# cerberus.net
KiCad netlist of a schematic drawn in EAGLE
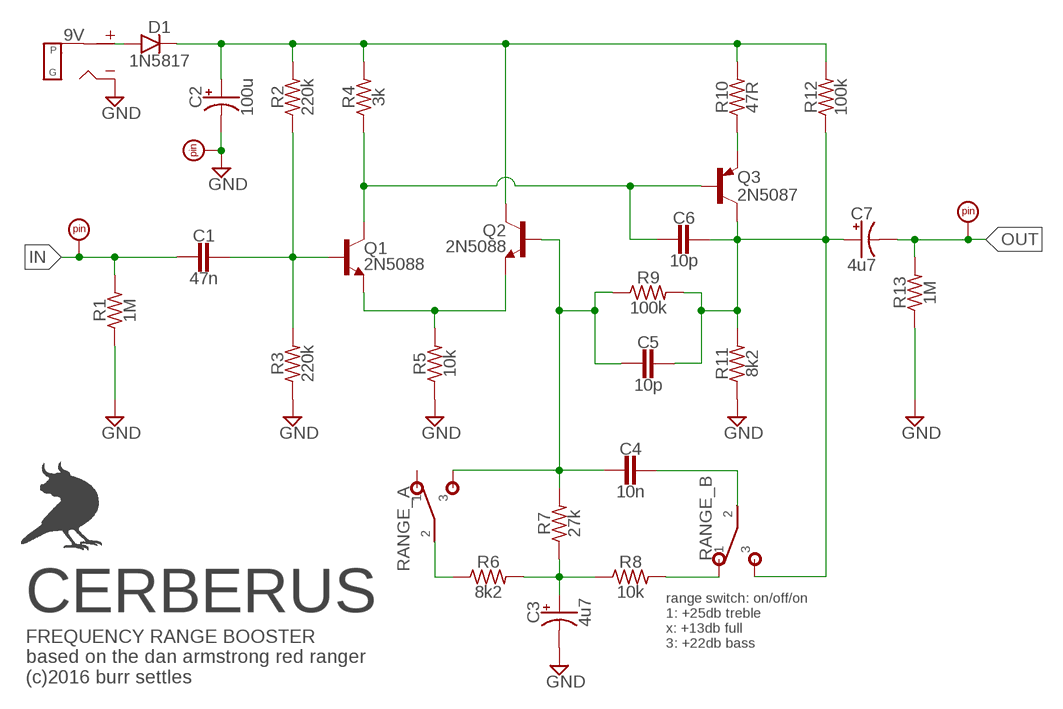
[diagram p0: schematic, sheet 1]

(export (version "E")
  (design (tool "Eeschema 10.0.6"))
  (components
    (comp (ref "9V")
      (value "DC_MONO")
      (footprint "eagle-import:DC")
      (libsource (lib "eagle-import") (part "DC_MONO"))
    )
    (comp (ref "C1")
      (value "47n")
      (footprint "eagle-import:BOX_SMALL")
      (libsource (lib "eagle-import") (part "CER/FILMBOX.1"))
    )
    (comp (ref "C2")
      (value "100u")
      (footprint "eagle-import:050_020_1")
      (libsource (lib "eagle-import") (part "0501"))
    )
    (comp (ref "C3")
      (value "4u7")
      (footprint "eagle-import:050_020_1")
      (libsource (lib "eagle-import") (part "0501"))
    )
    (comp (ref "C4")
      (value "10n")
      (footprint "eagle-import:BOX_SMALL")
      (libsource (lib "eagle-import") (part "CER/FILMBOX.1"))
    )
    (comp (ref "C5")
      (value "10p")
      (footprint "eagle-import:050X030_025_2")
      (libsource (lib "eagle-import") (part "CER/FILM2"))
    )
    (comp (ref "C6")
      (value "10p")
      (footprint "eagle-import:050X030_025_2")
      (libsource (lib "eagle-import") (part "CER/FILM2"))
    )
    (comp (ref "C7")
      (value "4u7")
      (footprint "eagle-import:050_020_1")
      (libsource (lib "eagle-import") (part "0501"))
    )
    (comp (ref "D1")
      (value "1N5817")
      (footprint "eagle-import:DO41-3")
      (libsource (lib "eagle-import") (part "DO41.3"))
    )
    (comp (ref "GND")
      (value "PADRND")
      (footprint "eagle-import:ROUND")
      (libsource (lib "eagle-import") (part "PADRND"))
    )
    (comp (ref "IN")
      (value "PADSQR")
      (footprint "eagle-import:SQUARE")
      (libsource (lib "eagle-import") (part "PADSQR"))
    )
    (comp (ref "OUT")
      (value "PADSQR")
      (footprint "eagle-import:SQUARE")
      (libsource (lib "eagle-import") (part "PADSQR"))
    )
    (comp (ref "Q1")
      (value "2N5088")
      (footprint "eagle-import:TO92-")
      (libsource (lib "eagle-import") (part "2N5088"))
    )
    (comp (ref "Q2")
      (value "2N5088")
      (footprint "eagle-import:TO92-")
      (libsource (lib "eagle-import") (part "2N5088"))
    )
    (comp (ref "Q3")
      (value "2N5087")
      (footprint "eagle-import:TO92-")
      (libsource (lib "eagle-import") (part "2N5087.1"))
    )
    (comp (ref "R1")
      (value "1M")
      (footprint "eagle-import:R0207_3")
      (libsource (lib "eagle-import") (part "R_.3B"))
    )
    (comp (ref "R2")
      (value "220k")
      (footprint "eagle-import:R0207_3")
      (libsource (lib "eagle-import") (part "R_.3B"))
    )
    (comp (ref "R3")
      (value "220k")
      (footprint "eagle-import:R0207_3")
      (libsource (lib "eagle-import") (part "R_.3B"))
    )
    (comp (ref "R4")
      (value "3k")
      (footprint "eagle-import:R0207_3")
      (libsource (lib "eagle-import") (part "R_.3B"))
    )
    (comp (ref "R5")
      (value "10k")
      (footprint "eagle-import:R0207_3")
      (libsource (lib "eagle-import") (part "R_.3B"))
    )
    (comp (ref "R6")
      (value "8k2")
      (footprint "eagle-import:R0207_3")
      (libsource (lib "eagle-import") (part "R_.3B"))
    )
    (comp (ref "R7")
      (value "27k")
      (footprint "eagle-import:R0207_3")
      (libsource (lib "eagle-import") (part "R_.3B"))
    )
    (comp (ref "R8")
      (value "10k")
      (footprint "eagle-import:R0207_3")
      (libsource (lib "eagle-import") (part "R_.3B"))
    )
    (comp (ref "R9")
      (value "100k")
      (footprint "eagle-import:R0207_3")
      (libsource (lib "eagle-import") (part "R_.3B"))
    )
    (comp (ref "R10")
      (value "47R")
      (footprint "eagle-import:R0207_3")
      (libsource (lib "eagle-import") (part "R_.3B"))
    )
    (comp (ref "R11")
      (value "8k2")
      (footprint "eagle-import:R0207_3")
      (libsource (lib "eagle-import") (part "R_.3B"))
    )
    (comp (ref "R12")
      (value "100k")
      (footprint "eagle-import:R0207_3")
      (libsource (lib "eagle-import") (part "R_.3B"))
    )
    (comp (ref "R13")
      (value "1M")
      (footprint "eagle-import:R0207_3")
      (libsource (lib "eagle-import") (part "R_.3B"))
    )
    (comp (ref "RANGE")
      (value "DPDT")
      (footprint "eagle-import:DPDT_PADS")
      (libsource (lib "eagle-import") (part "DPDTPADS"))
    )
  )
  (nets
    (net (code "1") (name "GND") (class "Default")
      (node (ref "9V") (pin "S") (pinfunction "SLEEVE_S") (pintype "passive"))
      (node (ref "C2") (pin "-") (pinfunction "-_-") (pintype "passive"))
      (node (ref "C3") (pin "-") (pinfunction "-_-") (pintype "passive"))
      (node (ref "GND") (pin "1") (pinfunction "P$1_1") (pintype "bidirectional"))
      (node (ref "R1") (pin "1") (pinfunction "1_1") (pintype "passive"))
      (node (ref "R11") (pin "1") (pinfunction "1_1") (pintype "passive"))
      (node (ref "R13") (pin "1") (pinfunction "1_1") (pintype "passive"))
      (node (ref "R3") (pin "1") (pinfunction "1_1") (pintype "passive"))
      (node (ref "R5") (pin "1") (pinfunction "1_1") (pintype "passive"))
    )
    (net (code "2") (name "IN") (class "Default")
      (node (ref "C1") (pin "2") (pinfunction "2_2") (pintype "passive"))
      (node (ref "IN") (pin "1") (pinfunction "P$1_1") (pintype "bidirectional"))
      (node (ref "R1") (pin "2") (pinfunction "2_2") (pintype "passive"))
    )
    (net (code "3") (name "Net-(9V-TIP)") (class "Default")
      (node (ref "9V") (pin "T") (pinfunction "TIP_T") (pintype "passive"))
      (node (ref "D1") (pin "A") (pinfunction "A_A") (pintype "passive"))
    )
    (net (code "4") (name "Net-(C3-Pad+)") (class "Default")
      (node (ref "C3") (pin "+") (pinfunction "+_+") (pintype "passive"))
      (node (ref "R6") (pin "2") (pinfunction "2_2") (pintype "passive"))
      (node (ref "R7") (pin "1") (pinfunction "1_1") (pintype "passive"))
      (node (ref "R8") (pin "1") (pinfunction "1_1") (pintype "passive"))
    )
    (net (code "5") (name "Net-(Q1-B)") (class "Default")
      (node (ref "C1") (pin "1") (pinfunction "1_1") (pintype "passive"))
      (node (ref "Q1") (pin "2") (pinfunction "B_2") (pintype "passive"))
      (node (ref "R2") (pin "1") (pinfunction "1_1") (pintype "passive"))
      (node (ref "R3") (pin "2") (pinfunction "2_2") (pintype "passive"))
    )
    (net (code "6") (name "Net-(Q1-C)") (class "Default")
      (node (ref "C6") (pin "2") (pinfunction "2_2") (pintype "passive"))
      (node (ref "Q1") (pin "1") (pinfunction "C_1") (pintype "passive"))
      (node (ref "Q3") (pin "2") (pinfunction "B_2") (pintype "passive"))
      (node (ref "R4") (pin "1") (pinfunction "1_1") (pintype "passive"))
    )
    (net (code "7") (name "Net-(Q1-E)") (class "Default")
      (node (ref "Q1") (pin "3") (pinfunction "E_3") (pintype "passive"))
      (node (ref "Q2") (pin "3") (pinfunction "E_3") (pintype "passive"))
      (node (ref "R5") (pin "2") (pinfunction "2_2") (pintype "passive"))
    )
    (net (code "8") (name "Net-(Q2-B)") (class "Default")
      (node (ref "C4") (pin "2") (pinfunction "2_2") (pintype "passive"))
      (node (ref "C5") (pin "2") (pinfunction "2_2") (pintype "passive"))
      (node (ref "Q2") (pin "2") (pinfunction "B_2") (pintype "passive"))
      (node (ref "R7") (pin "2") (pinfunction "2_2") (pintype "passive"))
      (node (ref "R9") (pin "1") (pinfunction "1_1") (pintype "passive"))
      (node (ref "RANGE") (pin "P$3") (pinfunction "3_P$3") (pintype "passive"))
    )
    (net (code "9") (name "Net-(Q2-C)") (class "Default")
      (node (ref "C2") (pin "+") (pinfunction "+_+") (pintype "passive"))
      (node (ref "D1") (pin "C") (pinfunction "C_C") (pintype "passive"))
      (node (ref "Q2") (pin "1") (pinfunction "C_1") (pintype "passive"))
      (node (ref "R10") (pin "2") (pinfunction "2_2") (pintype "passive"))
      (node (ref "R12") (pin "2") (pinfunction "2_2") (pintype "passive"))
      (node (ref "R2") (pin "2") (pinfunction "2_2") (pintype "passive"))
      (node (ref "R4") (pin "2") (pinfunction "2_2") (pintype "passive"))
    )
    (net (code "10") (name "Net-(Q3-C)") (class "Default")
      (node (ref "C5") (pin "1") (pinfunction "1_1") (pintype "passive"))
      (node (ref "C6") (pin "1") (pinfunction "1_1") (pintype "passive"))
      (node (ref "C7") (pin "+") (pinfunction "+_+") (pintype "passive"))
      (node (ref "Q3") (pin "1") (pinfunction "C_1") (pintype "passive"))
      (node (ref "R11") (pin "2") (pinfunction "2_2") (pintype "passive"))
      (node (ref "R12") (pin "1") (pinfunction "1_1") (pintype "passive"))
      (node (ref "R9") (pin "2") (pinfunction "2_2") (pintype "passive"))
      (node (ref "RANGE") (pin "P$6") (pinfunction "3_P$6") (pintype "passive"))
    )
    (net (code "11") (name "Net-(Q3-E)") (class "Default")
      (node (ref "Q3") (pin "3") (pinfunction "E_3") (pintype "passive"))
      (node (ref "R10") (pin "1") (pinfunction "1_1") (pintype "passive"))
    )
    (net (code "12") (name "Net-(RANGEA-2)") (class "Default")
      (node (ref "R6") (pin "1") (pinfunction "1_1") (pintype "passive"))
      (node (ref "RANGE") (pin "P$2") (pinfunction "2_P$2") (pintype "passive"))
    )
    (net (code "13") (name "Net-(RANGEB-1)") (class "Default")
      (node (ref "R8") (pin "2") (pinfunction "2_2") (pintype "passive"))
      (node (ref "RANGE") (pin "P$4") (pinfunction "1_P$4") (pintype "passive"))
    )
    (net (code "14") (name "Net-(RANGEB-2)") (class "Default")
      (node (ref "C4") (pin "1") (pinfunction "1_1") (pintype "passive"))
      (node (ref "RANGE") (pin "P$5") (pinfunction "2_P$5") (pintype "passive"))
    )
    (net (code "15") (name "OUT") (class "Default")
      (node (ref "C7") (pin "-") (pinfunction "-_-") (pintype "passive"))
      (node (ref "OUT") (pin "1") (pinfunction "P$1_1") (pintype "bidirectional"))
      (node (ref "R13") (pin "2") (pinfunction "2_2") (pintype "passive"))
    )
    (net (code "16") (name "unconnected-(RANGEA-1-PadP$1)") (class "Default")
      (node (ref "RANGE") (pin "P$1") (pinfunction "1_P$1") (pintype "passive"))
    )
  )
)
